# ArduinoPowerLogger.net
KiCad netlist of a schematic drawn in EasyEDA
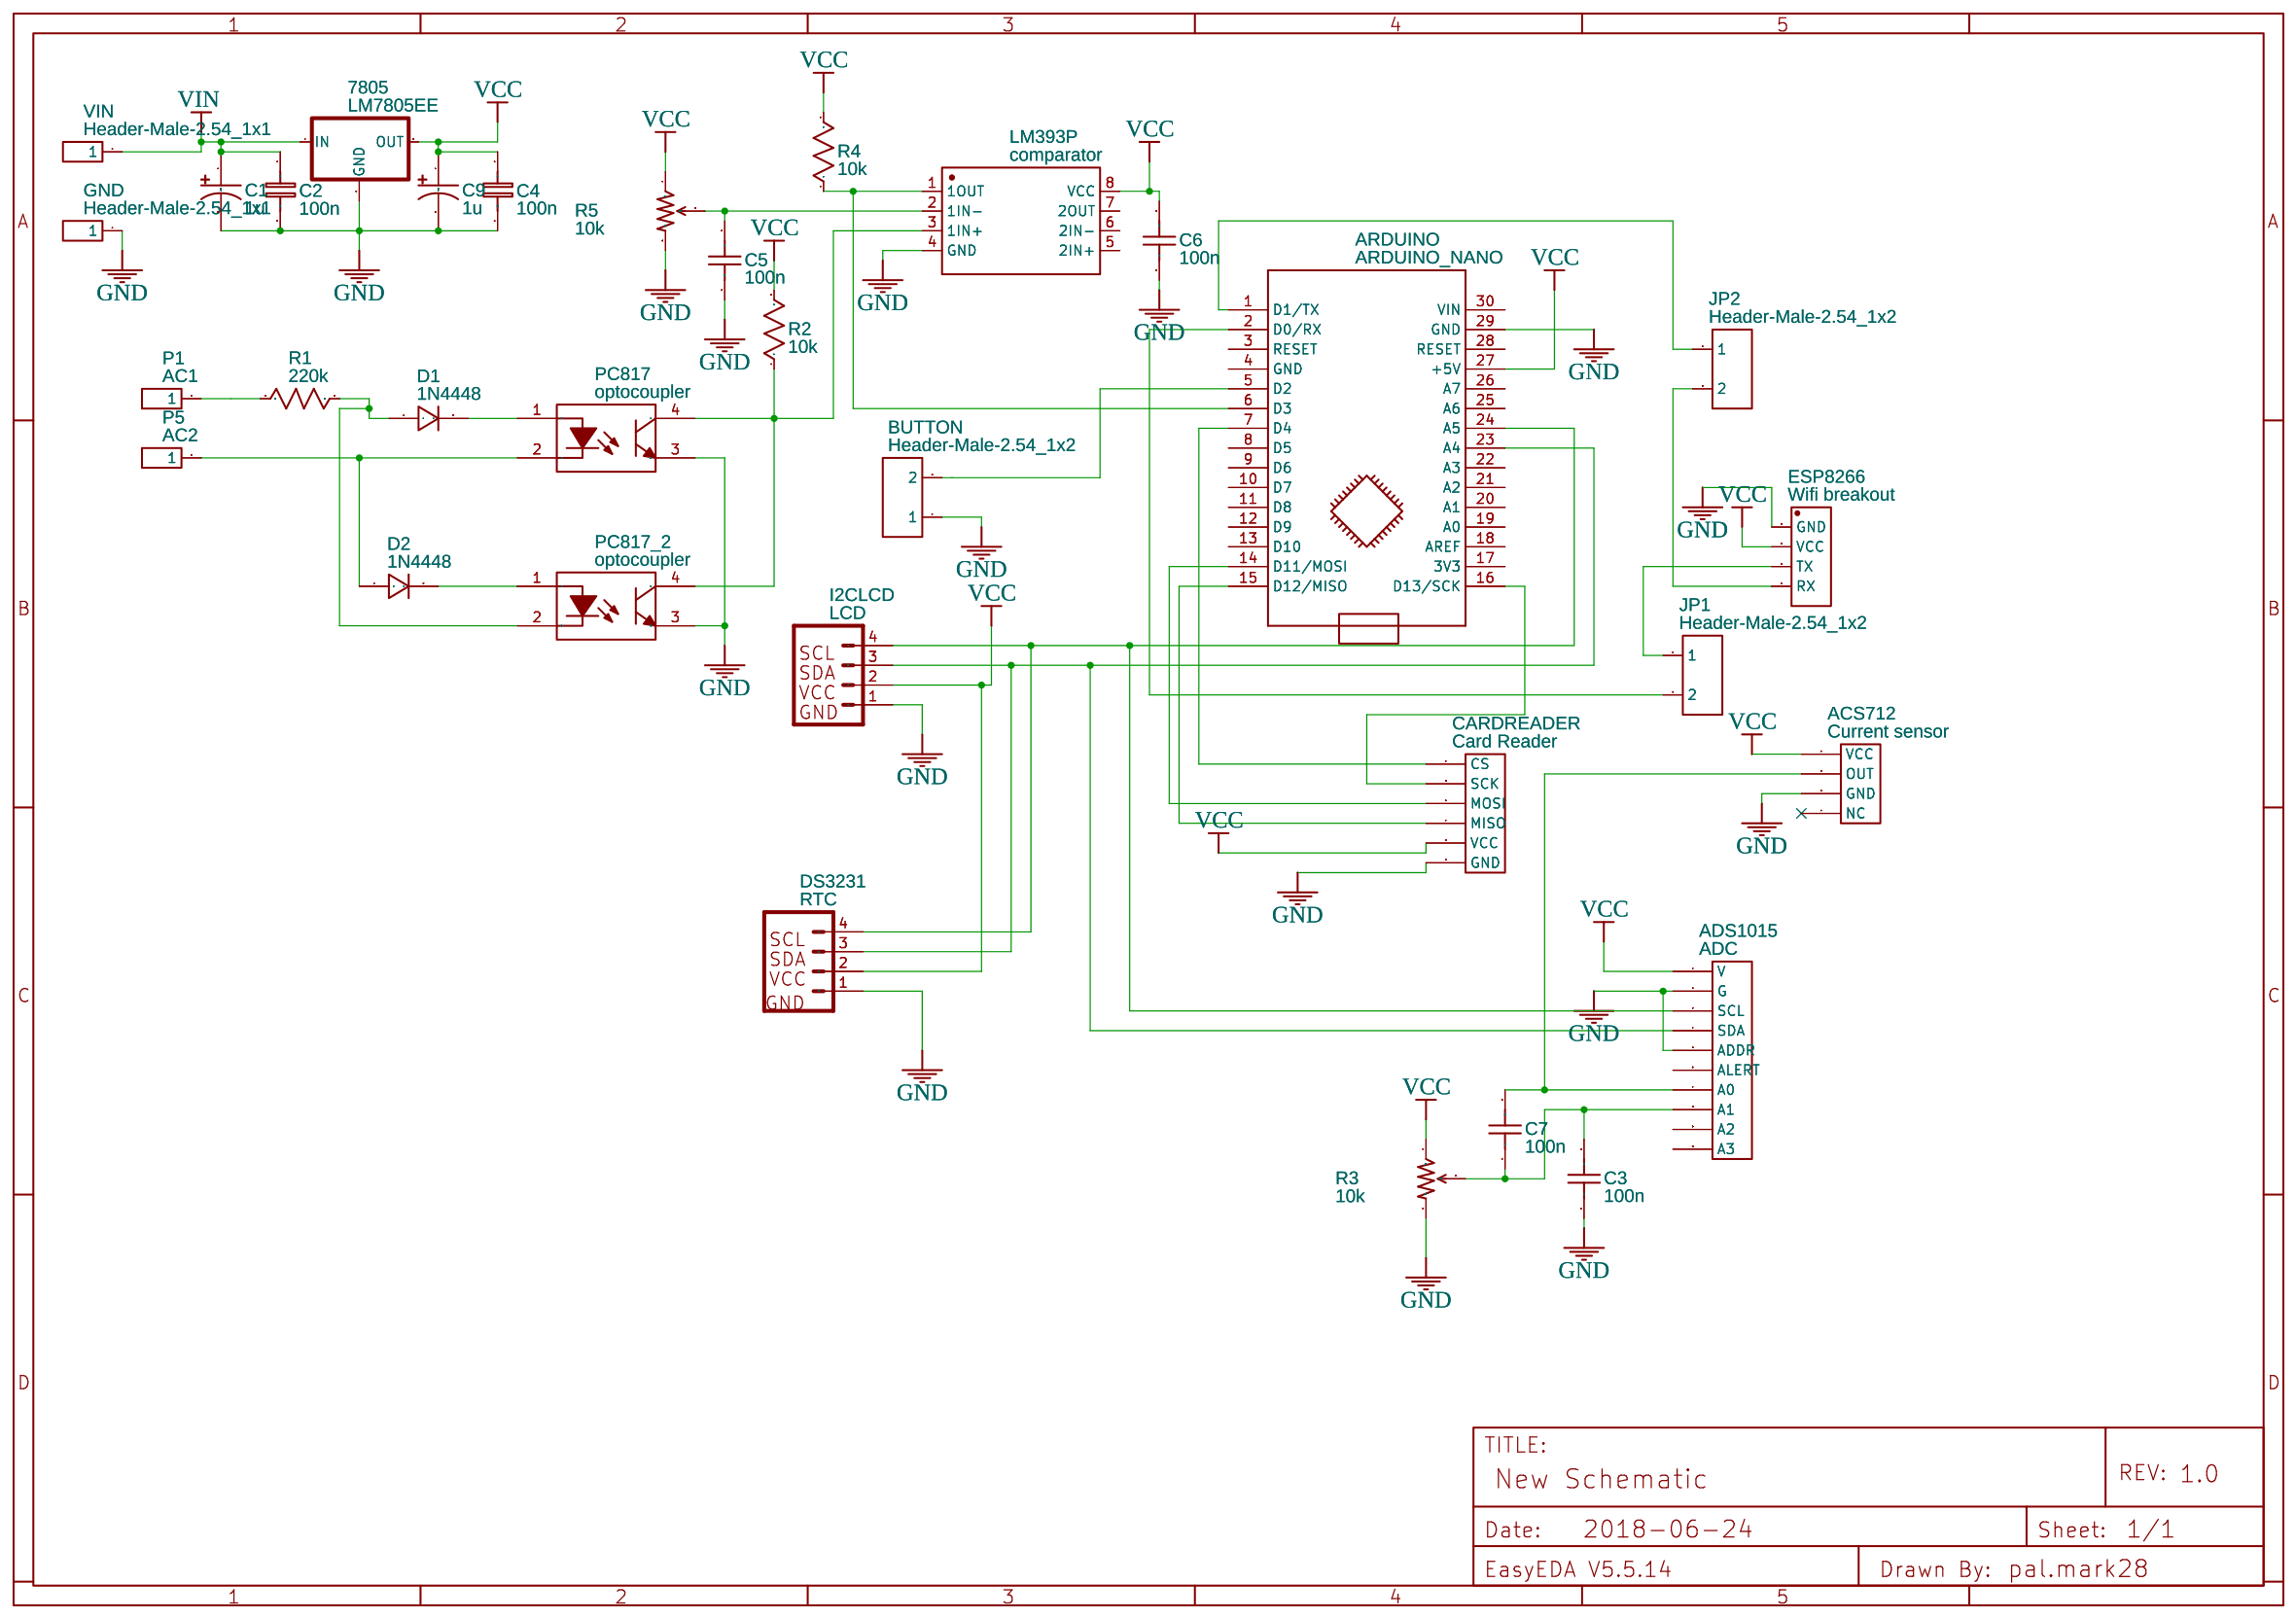
[diagram p0: schematic sheet]

(export (version "E")
  (design (tool "Eeschema 10.0.6"))
  (components
    (comp (ref "7805")
      (value "LM7805EE")
      (fields (field (name "BOM_Manufacturer Part") "?"))
      (libsource (lib "") (part "78XX"))
    )
    (comp (ref "ACS712")
      (value "Current sensor")
      (fields (field (name "BOM_Manufacturer Part") "Female header pitch2.54mm"))
      (libsource (lib "") (part "Unknown_915_395"))
    )
    (comp (ref "ADS1015")
      (value "ADC")
      (fields (field (name "BOM_Manufacturer Part") "2.54mm 1*10P Straight Female header Gold-plated"))
      (libsource (lib "") (part "Unknown_850_525"))
    )
    (comp (ref "ARDUINO")
      (value "ARDUINO_NANO")
      (fields (field (name "BOM_Manufacturer Part") "?"))
      (libsource (lib "") (part "Unknown_685_220"))
    )
    (comp (ref "BUTTON")
      (value "Header-Male-2.54_1x2")
      (fields (field (name "BOM_Manufacturer Part") "826629-2"))
      (libsource (lib "") (part "Unknown_450_245"))
    )
    (comp (ref "C1")
      (value "1u")
      (fields (field (name "BOM_Manufacturer Part") "?"))
      (libsource (lib "") (part "Cap_Electrolytic(TH)_D6.3XF2.5_US"))
    )
    (comp (ref "C2")
      (value "100n")
      (fields (field (name "BOM_Manufacturer Part") "?"))
      (libsource (lib "") (part "Cap_RAD-0.1_EU"))
    )
    (comp (ref "C3")
      (value "100n")
      (fields (field (name "BOM_Manufacturer Part") "?"))
      (libsource (lib "") (part "Cap_RAD-0.1_US"))
    )
    (comp (ref "C4")
      (value "100n")
      (fields (field (name "BOM_Manufacturer Part") "?"))
      (libsource (lib "") (part "Cap_RAD-0.1_EU_1"))
    )
    (comp (ref "C5")
      (value "100n")
      (fields (field (name "BOM_Manufacturer Part") "?"))
      (libsource (lib "") (part "Cap_RAD-0.1_US"))
    )
    (comp (ref "C6")
      (value "100n")
      (fields (field (name "BOM_Manufacturer Part") "?"))
      (libsource (lib "") (part "Cap_RAD-0.1_US"))
    )
    (comp (ref "C7")
      (value "100n")
      (fields (field (name "BOM_Manufacturer Part") "?"))
      (libsource (lib "") (part "Cap_RAD-0.1_US"))
    )
    (comp (ref "C9")
      (value "1u")
      (fields (field (name "BOM_Manufacturer Part") "?"))
      (libsource (lib "") (part "Cap_Electrolytic(TH)_D6.3XF2.5_US"))
    )
    (comp (ref "CARDREADER")
      (value "Card Reader")
      (fields (field (name "BOM_Manufacturer Part") "Female header 1*6p"))
      (libsource (lib "") (part "Unknown_725_400"))
    )
    (comp (ref "D1") (value "1N4448") (libsource (lib "") (part "Unknown_210_205")))
    (comp (ref "D2") (value "1N4448") (libsource (lib "") (part "Unknown_195_290")))
    (comp (ref "DS3231")
      (value "RTC")
      (fields (field (name "BOM_Manufacturer Part") "?"))
      (libsource (lib "") (part "Unknown_390_505"))
    )
    (comp (ref "ESP8266")
      (value "Wifi breakout")
      (fields (field (name "BOM_Manufacturer Part") "210S-1*4P L=11.6MMGold-plated black"))
      (libsource (lib "") (part "Unknown_905_275"))
    )
    (comp (ref "GND") (value "Header-Male-2.54_1x1") (libsource (lib "") (part "Unknown_40_110")))
    (comp (ref "I2CLCD")
      (value "LCD")
      (fields (field (name "BOM_Manufacturer Part") "?"))
      (libsource (lib "") (part "Unknown_405_360"))
    )
    (comp (ref "JP1")
      (value "Header-Male-2.54_1x2")
      (fields (field (name "BOM_Manufacturer Part") "826629-2"))
      (libsource (lib "") (part "Unknown_855_335"))
    )
    (comp (ref "JP2")
      (value "Header-Male-2.54_1x2")
      (fields (field (name "BOM_Manufacturer Part") "826629-2"))
      (libsource (lib "") (part "Unknown_870_180"))
    )
    (comp (ref "LM393P")
      (value "comparator")
      (fields (field (name "BOM_Manufacturer Part") "LM393P"))
      (libsource (lib "") (part "Unknown_510_80"))
    )
    (comp (ref "P1")
      (value "AC1")
      (fields (field (name "BOM_Manufacturer Part") "Header-Male-2.54_1x1"))
      (libsource (lib "") (part "Unknown_80_195"))
    )
    (comp (ref "P5")
      (value "AC2")
      (fields (field (name "BOM_Manufacturer Part") "Header-Male-2.54_1x1"))
      (libsource (lib "") (part "Unknown_80_225"))
    )
    (comp (ref "PC817")
      (value "optocoupler")
      (fields (field (name "BOM_Manufacturer Part") "PC817X2NSZ9F(B)"))
      (libsource (lib "") (part "Unknown_305_215"))
    )
    (comp (ref "PC817_2")
      (value "optocoupler")
      (fields (field (name "BOM_Manufacturer Part") "PC817X2NSZ9F(B)"))
      (libsource (lib "") (part "Unknown_305_300"))
    )
    (comp (ref "R1")
      (value "220k")
      (fields (field (name "BOM_Manufacturer Part") "?"))
      (libsource (lib "") (part "Res_AXIAL-0.3(1/8W)_US"))
    )
    (comp (ref "R2")
      (value "10k")
      (fields (field (name "BOM_Manufacturer Part") "?"))
      (libsource (lib "") (part "Res_AXIAL-0.3(1/8W)_US_1"))
    )
    (comp (ref "R3")
      (value "10k")
      (fields (field (name "BOM_Manufacturer Part") "?"))
      (libsource (lib "") (part "Unknown_715_590"))
    )
    (comp (ref "R4")
      (value "10k")
      (fields (field (name "BOM_Manufacturer Part") "?"))
      (libsource (lib "") (part "Res_AXIAL-0.3(1/8W)_US_1"))
    )
    (comp (ref "R5")
      (value "10k")
      (fields (field (name "BOM_Manufacturer Part") "?"))
      (libsource (lib "") (part "Unknown_330_100"))
    )
    (comp (ref "VIN") (value "Header-Male-2.54_1x1") (libsource (lib "") (part "Unknown_40_70")))
  )
  (nets
    (net (code "1") (name "GND") (class "Default")
      (node (ref "7805") (pin "2") (pinfunction "GND_2") (pintype "unspecified"))
      (node (ref "ACS712") (pin "3") (pinfunction "GND_3") (pintype "input"))
      (node (ref "ADS1015") (pin "2") (pinfunction "G_2") (pintype "input"))
      (node (ref "ADS1015") (pin "5") (pinfunction "ADDR_5") (pintype "input"))
      (node (ref "ARDUINO") (pin "29") (pinfunction "GND_29") (pintype "unspecified"))
      (node (ref "BUTTON") (pin "1") (pinfunction "1_1") (pintype "unspecified"))
      (node (ref "C1") (pin "2") (pinfunction "2_2") (pintype "unspecified"))
      (node (ref "C2") (pin "2") (pinfunction "2_2") (pintype "unspecified"))
      (node (ref "C3") (pin "1") (pinfunction "1_1") (pintype "unspecified"))
      (node (ref "C4") (pin "2") (pinfunction "2_2") (pintype "unspecified"))
      (node (ref "C5") (pin "1") (pinfunction "1_1") (pintype "unspecified"))
      (node (ref "C6") (pin "1") (pinfunction "1_1") (pintype "unspecified"))
      (node (ref "C9") (pin "2") (pinfunction "2_2") (pintype "unspecified"))
      (node (ref "CARDREADER") (pin "6") (pinfunction "GND_6") (pintype "input"))
      (node (ref "DS3231") (pin "1") (pinfunction "1_1") (pintype "unspecified"))
      (node (ref "ESP8266") (pin "1") (pinfunction "GND_1") (pintype "unspecified"))
      (node (ref "GND") (pin "1") (pinfunction "1_1") (pintype "input"))
      (node (ref "I2CLCD") (pin "1") (pinfunction "1_1") (pintype "unspecified"))
      (node (ref "LM393P") (pin "4") (pinfunction "GND_4") (pintype "unspecified"))
      (node (ref "PC817") (pin "3") (pinfunction "3_3") (pintype "unspecified"))
      (node (ref "PC817_2") (pin "3") (pinfunction "3_3") (pintype "unspecified"))
      (node (ref "R3") (pin "3") (pinfunction "CW_3") (pintype "unspecified"))
      (node (ref "R5") (pin "3") (pinfunction "CW_3") (pintype "unspecified"))
    )
    (net (code "2") (name "Net-(ACS712-OUT)") (class "Default")
      (node (ref "ACS712") (pin "2") (pinfunction "OUT_2") (pintype "input"))
      (node (ref "ADS1015") (pin "7") (pinfunction "A0_7") (pintype "input"))
      (node (ref "C7") (pin "2") (pinfunction "2_2") (pintype "unspecified"))
    )
    (net (code "3") (name "Net-(ADS1015-A1)") (class "Default")
      (node (ref "ADS1015") (pin "8") (pinfunction "A1_8") (pintype "input"))
      (node (ref "C3") (pin "2") (pinfunction "2_2") (pintype "unspecified"))
      (node (ref "C7") (pin "1") (pinfunction "1_1") (pintype "unspecified"))
      (node (ref "R3") (pin "2") (pinfunction "WIPER_2") (pintype "unspecified"))
    )
    (net (code "4") (name "Net-(ADS1015-SCL)") (class "Default")
      (node (ref "ADS1015") (pin "3") (pinfunction "SCL_3") (pintype "input"))
      (node (ref "ARDUINO") (pin "24") (pinfunction "A5_24") (pintype "unspecified"))
      (node (ref "DS3231") (pin "4") (pinfunction "4_4") (pintype "unspecified"))
      (node (ref "I2CLCD") (pin "4") (pinfunction "4_4") (pintype "unspecified"))
    )
    (net (code "5") (name "Net-(ADS1015-SDA)") (class "Default")
      (node (ref "ADS1015") (pin "4") (pinfunction "SDA_4") (pintype "input"))
      (node (ref "ARDUINO") (pin "23") (pinfunction "A4_23") (pintype "unspecified"))
      (node (ref "DS3231") (pin "3") (pinfunction "3_3") (pintype "unspecified"))
      (node (ref "I2CLCD") (pin "3") (pinfunction "3_3") (pintype "unspecified"))
    )
    (net (code "6") (name "Net-(ARDUINO-D0{slash}RX)") (class "Default")
      (node (ref "ARDUINO") (pin "2") (pinfunction "D0/RX_2") (pintype "unspecified"))
      (node (ref "JP1") (pin "2") (pinfunction "2_2") (pintype "unspecified"))
    )
    (net (code "7") (name "Net-(ARDUINO-D1{slash}TX)") (class "Default")
      (node (ref "ARDUINO") (pin "1") (pinfunction "D1/TX_1") (pintype "unspecified"))
      (node (ref "JP2") (pin "1") (pinfunction "1_1") (pintype "unspecified"))
    )
    (net (code "8") (name "Net-(ARDUINO-D2)") (class "Default")
      (node (ref "ARDUINO") (pin "5") (pinfunction "D2_5") (pintype "unspecified"))
      (node (ref "BUTTON") (pin "2") (pinfunction "2_2") (pintype "unspecified"))
    )
    (net (code "9") (name "Net-(ARDUINO-D3)") (class "Default")
      (node (ref "ARDUINO") (pin "6") (pinfunction "D3_6") (pintype "unspecified"))
      (node (ref "LM393P") (pin "1") (pinfunction "1OUT_1") (pintype "unspecified"))
      (node (ref "R4") (pin "1") (pinfunction "1_1") (pintype "unspecified"))
    )
    (net (code "10") (name "Net-(ARDUINO-D4)") (class "Default")
      (node (ref "ARDUINO") (pin "7") (pinfunction "D4_7") (pintype "unspecified"))
      (node (ref "CARDREADER") (pin "1") (pinfunction "CS_1") (pintype "input"))
    )
    (net (code "11") (name "Net-(ARDUINO-D11{slash}MOSI)") (class "Default")
      (node (ref "ARDUINO") (pin "14") (pinfunction "D11/MOSI_14") (pintype "unspecified"))
      (node (ref "CARDREADER") (pin "3") (pinfunction "MOSI_3") (pintype "input"))
    )
    (net (code "12") (name "Net-(ARDUINO-D12{slash}MISO)") (class "Default")
      (node (ref "ARDUINO") (pin "15") (pinfunction "D12/MISO_15") (pintype "unspecified"))
      (node (ref "CARDREADER") (pin "4") (pinfunction "MISO_4") (pintype "input"))
    )
    (net (code "13") (name "Net-(ARDUINO-D13{slash}SCK)") (class "Default")
      (node (ref "ARDUINO") (pin "16") (pinfunction "D13/SCK_16") (pintype "unspecified"))
      (node (ref "CARDREADER") (pin "2") (pinfunction "SCK_2") (pintype "input"))
    )
    (net (code "14") (name "Net-(D1-A)") (class "Default")
      (node (ref "D1") (pin "1") (pinfunction "A_1") (pintype "unspecified"))
      (node (ref "PC817_2") (pin "2") (pinfunction "2_2") (pintype "unspecified"))
      (node (ref "R1") (pin "2") (pinfunction "2_2") (pintype "unspecified"))
    )
    (net (code "15") (name "Net-(D1-K)") (class "Default")
      (node (ref "D1") (pin "2") (pinfunction "K_2") (pintype "unspecified"))
      (node (ref "PC817") (pin "1") (pinfunction "1_1") (pintype "unspecified"))
    )
    (net (code "16") (name "Net-(D2-A)") (class "Default")
      (node (ref "D2") (pin "1") (pinfunction "A_1") (pintype "unspecified"))
      (node (ref "P5") (pin "1") (pinfunction "1_1") (pintype "input"))
      (node (ref "PC817") (pin "2") (pinfunction "2_2") (pintype "unspecified"))
    )
    (net (code "17") (name "Net-(D2-K)") (class "Default")
      (node (ref "D2") (pin "2") (pinfunction "K_2") (pintype "unspecified"))
      (node (ref "PC817_2") (pin "1") (pinfunction "1_1") (pintype "unspecified"))
    )
    (net (code "18") (name "Net-(ESP8266-RX)") (class "Default")
      (node (ref "ESP8266") (pin "4") (pinfunction "RX_4") (pintype "unspecified"))
      (node (ref "JP2") (pin "2") (pinfunction "2_2") (pintype "unspecified"))
    )
    (net (code "19") (name "Net-(ESP8266-TX)") (class "Default")
      (node (ref "ESP8266") (pin "3") (pinfunction "TX_3") (pintype "unspecified"))
      (node (ref "JP1") (pin "1") (pinfunction "1_1") (pintype "unspecified"))
    )
    (net (code "20") (name "Net-(LM393P-1IN+)") (class "Default")
      (node (ref "LM393P") (pin "3") (pinfunction "1IN+_3") (pintype "unspecified"))
      (node (ref "PC817") (pin "4") (pinfunction "4_4") (pintype "unspecified"))
      (node (ref "PC817_2") (pin "4") (pinfunction "4_4") (pintype "unspecified"))
      (node (ref "R2") (pin "1") (pinfunction "1_1") (pintype "unspecified"))
    )
    (net (code "21") (name "Net-(LM393P-1IN-)") (class "Default")
      (node (ref "C5") (pin "2") (pinfunction "2_2") (pintype "unspecified"))
      (node (ref "LM393P") (pin "2") (pinfunction "1IN-_2") (pintype "unspecified"))
      (node (ref "R5") (pin "2") (pinfunction "WIPER_2") (pintype "unspecified"))
    )
    (net (code "22") (name "Net-(P1-Pad1)") (class "Default")
      (node (ref "P1") (pin "1") (pinfunction "1_1") (pintype "input"))
      (node (ref "R1") (pin "1") (pinfunction "1_1") (pintype "unspecified"))
    )
    (net (code "23") (name "VCC") (class "Default")
      (node (ref "7805") (pin "3") (pinfunction "OUT_3") (pintype "unspecified"))
      (node (ref "ACS712") (pin "1") (pinfunction "VCC_1") (pintype "input"))
      (node (ref "ADS1015") (pin "1") (pinfunction "V_1") (pintype "input"))
      (node (ref "ARDUINO") (pin "27") (pinfunction "+5V_27") (pintype "unspecified"))
      (node (ref "C4") (pin "1") (pinfunction "1_1") (pintype "unspecified"))
      (node (ref "C6") (pin "2") (pinfunction "2_2") (pintype "unspecified"))
      (node (ref "C9") (pin "1") (pinfunction "1_1") (pintype "unspecified"))
      (node (ref "CARDREADER") (pin "5") (pinfunction "VCC_5") (pintype "input"))
      (node (ref "DS3231") (pin "2") (pinfunction "2_2") (pintype "unspecified"))
      (node (ref "ESP8266") (pin "2") (pinfunction "VCC_2") (pintype "unspecified"))
      (node (ref "I2CLCD") (pin "2") (pinfunction "2_2") (pintype "unspecified"))
      (node (ref "LM393P") (pin "8") (pinfunction "VCC_8") (pintype "unspecified"))
      (node (ref "R2") (pin "2") (pinfunction "2_2") (pintype "unspecified"))
      (node (ref "R3") (pin "1") (pinfunction "CCW_1") (pintype "unspecified"))
      (node (ref "R4") (pin "2") (pinfunction "2_2") (pintype "unspecified"))
      (node (ref "R5") (pin "1") (pinfunction "CCW_1") (pintype "unspecified"))
    )
    (net (code "24") (name "VIN") (class "Default")
      (node (ref "7805") (pin "1") (pinfunction "IN_1") (pintype "unspecified"))
      (node (ref "C1") (pin "1") (pinfunction "1_1") (pintype "unspecified"))
      (node (ref "C2") (pin "1") (pinfunction "1_1") (pintype "unspecified"))
      (node (ref "VIN") (pin "1") (pinfunction "1_1") (pintype "input"))
    )
    (net (code "25") (name "unconnected-(ACS712-NC-Pad4)") (class "Default")
      (node (ref "ACS712") (pin "4") (pinfunction "NC_4") (pintype "input+no_connect"))
    )
    (net (code "26") (name "unconnected-(ADS1015-A2-Pad9)") (class "Default")
      (node (ref "ADS1015") (pin "9") (pinfunction "A2_9") (pintype "input"))
    )
    (net (code "27") (name "unconnected-(ADS1015-A3-Pad10)") (class "Default")
      (node (ref "ADS1015") (pin "10") (pinfunction "A3_10") (pintype "input"))
    )
    (net (code "28") (name "unconnected-(ADS1015-ALERT-Pad6)") (class "Default")
      (node (ref "ADS1015") (pin "6") (pinfunction "ALERT_6") (pintype "input"))
    )
    (net (code "29") (name "unconnected-(ARDUINO-3V3-Pad17)") (class "Default")
      (node (ref "ARDUINO") (pin "17") (pinfunction "3V3_17") (pintype "unspecified"))
    )
    (net (code "30") (name "unconnected-(ARDUINO-A0-Pad19)") (class "Default")
      (node (ref "ARDUINO") (pin "19") (pinfunction "A0_19") (pintype "unspecified"))
    )
    (net (code "31") (name "unconnected-(ARDUINO-A1-Pad20)") (class "Default")
      (node (ref "ARDUINO") (pin "20") (pinfunction "A1_20") (pintype "unspecified"))
    )
    (net (code "32") (name "unconnected-(ARDUINO-A2-Pad21)") (class "Default")
      (node (ref "ARDUINO") (pin "21") (pinfunction "A2_21") (pintype "unspecified"))
    )
    (net (code "33") (name "unconnected-(ARDUINO-A3-Pad22)") (class "Default")
      (node (ref "ARDUINO") (pin "22") (pinfunction "A3_22") (pintype "unspecified"))
    )
    (net (code "34") (name "unconnected-(ARDUINO-A6-Pad25)") (class "Default")
      (node (ref "ARDUINO") (pin "25") (pinfunction "A6_25") (pintype "unspecified"))
    )
    (net (code "35") (name "unconnected-(ARDUINO-A7-Pad26)") (class "Default")
      (node (ref "ARDUINO") (pin "26") (pinfunction "A7_26") (pintype "unspecified"))
    )
    (net (code "36") (name "unconnected-(ARDUINO-AREF-Pad18)") (class "Default")
      (node (ref "ARDUINO") (pin "18") (pinfunction "AREF_18") (pintype "unspecified"))
    )
    (net (code "37") (name "unconnected-(ARDUINO-D5-Pad8)") (class "Default")
      (node (ref "ARDUINO") (pin "8") (pinfunction "D5_8") (pintype "unspecified"))
    )
    (net (code "38") (name "unconnected-(ARDUINO-D6-Pad9)") (class "Default")
      (node (ref "ARDUINO") (pin "9") (pinfunction "D6_9") (pintype "unspecified"))
    )
    (net (code "39") (name "unconnected-(ARDUINO-D7-Pad10)") (class "Default")
      (node (ref "ARDUINO") (pin "10") (pinfunction "D7_10") (pintype "unspecified"))
    )
    (net (code "40") (name "unconnected-(ARDUINO-D8-Pad11)") (class "Default")
      (node (ref "ARDUINO") (pin "11") (pinfunction "D8_11") (pintype "unspecified"))
    )
    (net (code "41") (name "unconnected-(ARDUINO-D9-Pad12)") (class "Default")
      (node (ref "ARDUINO") (pin "12") (pinfunction "D9_12") (pintype "unspecified"))
    )
    (net (code "42") (name "unconnected-(ARDUINO-D10-Pad13)") (class "Default")
      (node (ref "ARDUINO") (pin "13") (pinfunction "D10_13") (pintype "unspecified"))
    )
    (net (code "43") (name "unconnected-(ARDUINO-GND-Pad4)") (class "Default")
      (node (ref "ARDUINO") (pin "4") (pinfunction "GND_4") (pintype "unspecified"))
    )
    (net (code "44") (name "unconnected-(ARDUINO-RESET-Pad3)") (class "Default")
      (node (ref "ARDUINO") (pin "3") (pinfunction "RESET_3") (pintype "unspecified"))
    )
    (net (code "45") (name "unconnected-(ARDUINO-RESET-Pad28)") (class "Default")
      (node (ref "ARDUINO") (pin "28") (pinfunction "RESET_28") (pintype "unspecified"))
    )
    (net (code "46") (name "unconnected-(ARDUINO-VIN-Pad30)") (class "Default")
      (node (ref "ARDUINO") (pin "30") (pinfunction "VIN_30") (pintype "unspecified"))
    )
    (net (code "47") (name "unconnected-(LM393P-2IN+-Pad5)") (class "Default")
      (node (ref "LM393P") (pin "5") (pinfunction "2IN+_5") (pintype "unspecified"))
    )
    (net (code "48") (name "unconnected-(LM393P-2IN--Pad6)") (class "Default")
      (node (ref "LM393P") (pin "6") (pinfunction "2IN-_6") (pintype "unspecified"))
    )
    (net (code "49") (name "unconnected-(LM393P-2OUT-Pad7)") (class "Default")
      (node (ref "LM393P") (pin "7") (pinfunction "2OUT_7") (pintype "unspecified"))
    )
  )
)
